# led-driver-v1.net
KiCad netlist of a schematic drawn in EAGLE
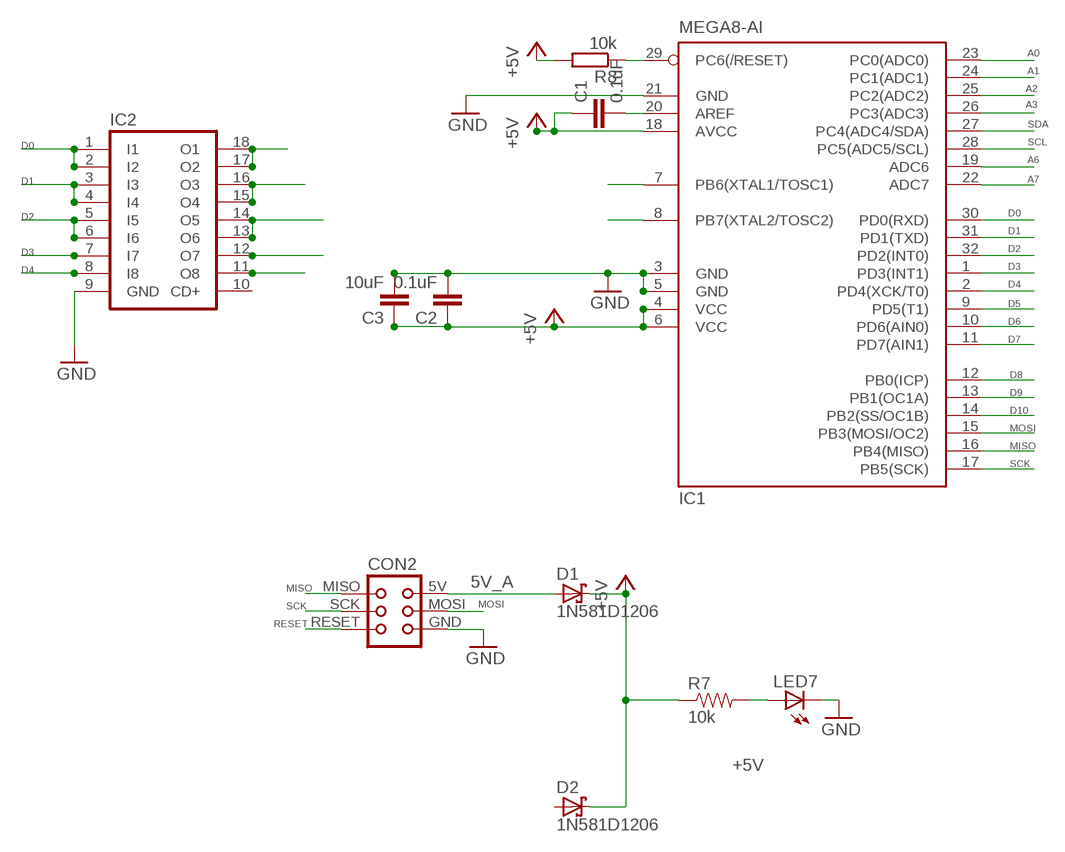
[diagram p0: schematic, sheet 1]

(export (version "E")
  (design (tool "Eeschema 10.0.6"))
  (components
    (comp (ref "C1")
      (value "0.1uF")
      (footprint "eagle-import:C1206")
      (libsource (lib "eagle-import") (part "C-EUC1206"))
    )
    (comp (ref "C2")
      (value "0.1uF")
      (footprint "eagle-import:C1206")
      (libsource (lib "eagle-import") (part "C-EUC1206"))
    )
    (comp (ref "C3")
      (value "10uF")
      (footprint "eagle-import:C1206")
      (libsource (lib "eagle-import") (part "C-EUC1206"))
    )
    (comp (ref "CON2")
      (value "TINYISPTAG")
      (footprint "eagle-import:TC2030-MCP")
      (libsource (lib "eagle-import") (part "TINYISPTAG"))
    )
    (comp (ref "D1")
      (value "1N581D1206")
      (footprint "eagle-import:LED-1206")
      (libsource (lib "eagle-import") (part "1N581D1206"))
    )
    (comp (ref "D2")
      (value "1N581D1206")
      (footprint "eagle-import:LED-1206")
      (libsource (lib "eagle-import") (part "1N581D1206"))
    )
    (comp (ref "IC1")
      (value "MEGA8-AI")
      (footprint "eagle-import:TQFP32-08")
      (fields (field (name "MPN") "ATMEGA8-16AU"))
      (libsource (lib "eagle-import") (part "MEGA8-AI"))
    )
    (comp (ref "IC2")
      (value "ULN2803A")
      (footprint "eagle-import:SO18W")
      (libsource (lib "eagle-import") (part "ULN2803A"))
    )
    (comp (ref "LED7")
      (value "LEDCHIP-LED0603")
      (footprint "eagle-import:CHIP-LED0603")
      (libsource (lib "eagle-import") (part "LEDCHIP-LED0603"))
    )
    (comp (ref "R7")
      (value "10k")
      (footprint "eagle-import:0603-RES")
      (libsource (lib "eagle-import") (part "RESISTOR0603-RES"))
    )
    (comp (ref "R8")
      (value "10k")
      (footprint "eagle-import:M1206")
      (libsource (lib "eagle-import") (part "R-EU_M1206"))
    )
  )
  (nets
    (net (code "1") (name "+5V") (class "Default")
      (node (ref "C1") (pin "1") (pinfunction "1_1") (pintype "passive"))
      (node (ref "C2") (pin "1") (pinfunction "1_1") (pintype "passive"))
      (node (ref "C3") (pin "1") (pinfunction "1_1") (pintype "passive"))
      (node (ref "D1") (pin "C") (pinfunction "C_C") (pintype "passive"))
      (node (ref "D2") (pin "C") (pinfunction "C_C") (pintype "passive"))
      (node (ref "IC1") (pin "18") (pinfunction "AVCC_18") (pintype "power_in"))
      (node (ref "IC1") (pin "4") (pinfunction "VCC_4") (pintype "power_in"))
      (node (ref "IC1") (pin "6") (pinfunction "VCC_6") (pintype "power_in"))
      (node (ref "R7") (pin "1") (pinfunction "1_1") (pintype "passive"))
      (node (ref "R8") (pin "2") (pinfunction "2_2") (pintype "passive"))
    )
    (net (code "2") (name "/5V_A") (class "Default")
      (node (ref "CON2") (pin "5V") (pinfunction "VCC_5V") (pintype "passive"))
      (node (ref "D1") (pin "A") (pinfunction "A_A") (pintype "passive"))
    )
    (net (code "3") (name "/A0") (class "Default")
      (node (ref "IC1") (pin "23") (pinfunction "PC0(ADC0)_23") (pintype "bidirectional"))
    )
    (net (code "4") (name "/A1") (class "Default")
      (node (ref "IC1") (pin "24") (pinfunction "PC1(ADC1)_24") (pintype "bidirectional"))
    )
    (net (code "5") (name "/A2") (class "Default")
      (node (ref "IC1") (pin "25") (pinfunction "PC2(ADC2)_25") (pintype "bidirectional"))
    )
    (net (code "6") (name "/A3") (class "Default")
      (node (ref "IC1") (pin "26") (pinfunction "PC3(ADC3)_26") (pintype "bidirectional"))
    )
    (net (code "7") (name "/A6") (class "Default")
      (node (ref "IC1") (pin "19") (pinfunction "ADC6_19") (pintype "bidirectional"))
    )
    (net (code "8") (name "/A7") (class "Default")
      (node (ref "IC1") (pin "22") (pinfunction "ADC7_22") (pintype "bidirectional"))
    )
    (net (code "9") (name "/D0") (class "Default")
      (node (ref "IC1") (pin "30") (pinfunction "PD0(RXD)_30") (pintype "bidirectional"))
      (node (ref "IC2") (pin "1") (pinfunction "I1_1") (pintype "input"))
      (node (ref "IC2") (pin "2") (pinfunction "I2_2") (pintype "input"))
    )
    (net (code "10") (name "/D1") (class "Default")
      (node (ref "IC1") (pin "31") (pinfunction "PD1(TXD)_31") (pintype "bidirectional"))
      (node (ref "IC2") (pin "3") (pinfunction "I3_3") (pintype "input"))
      (node (ref "IC2") (pin "4") (pinfunction "I4_4") (pintype "input"))
    )
    (net (code "11") (name "/D2") (class "Default")
      (node (ref "IC1") (pin "32") (pinfunction "PD2(INT0)_32") (pintype "bidirectional"))
      (node (ref "IC2") (pin "5") (pinfunction "I5_5") (pintype "input"))
      (node (ref "IC2") (pin "6") (pinfunction "I6_6") (pintype "input"))
    )
    (net (code "12") (name "/D3") (class "Default")
      (node (ref "IC1") (pin "1") (pinfunction "PD3(INT1)_1") (pintype "bidirectional"))
      (node (ref "IC2") (pin "7") (pinfunction "I7_7") (pintype "input"))
    )
    (net (code "13") (name "/D4") (class "Default")
      (node (ref "IC1") (pin "2") (pinfunction "PD4(XCK/T0)_2") (pintype "bidirectional"))
      (node (ref "IC2") (pin "8") (pinfunction "I8_8") (pintype "input"))
    )
    (net (code "14") (name "/D5") (class "Default")
      (node (ref "IC1") (pin "9") (pinfunction "PD5(T1)_9") (pintype "bidirectional"))
    )
    (net (code "15") (name "/D6") (class "Default")
      (node (ref "IC1") (pin "10") (pinfunction "PD6(AIN0)_10") (pintype "bidirectional"))
    )
    (net (code "16") (name "/D7") (class "Default")
      (node (ref "IC1") (pin "11") (pinfunction "PD7(AIN1)_11") (pintype "bidirectional"))
    )
    (net (code "17") (name "/D8") (class "Default")
      (node (ref "IC1") (pin "12") (pinfunction "PB0(ICP)_12") (pintype "bidirectional"))
    )
    (net (code "18") (name "/D9") (class "Default")
      (node (ref "IC1") (pin "13") (pinfunction "PB1(OC1A)_13") (pintype "bidirectional"))
    )
    (net (code "19") (name "/D10") (class "Default")
      (node (ref "IC1") (pin "14") (pinfunction "PB2(SS/OC1B)_14") (pintype "bidirectional"))
    )
    (net (code "20") (name "/MISO") (class "Default")
      (node (ref "CON2") (pin "MISO") (pinfunction "MISO_MISO") (pintype "passive"))
      (node (ref "IC1") (pin "16") (pinfunction "PB4(MISO)_16") (pintype "bidirectional"))
    )
    (net (code "21") (name "/MOSI") (class "Default")
      (node (ref "CON2") (pin "MOSI") (pinfunction "MOSI_MOSI") (pintype "passive"))
      (node (ref "IC1") (pin "15") (pinfunction "PB3(MOSI/OC2)_15") (pintype "bidirectional"))
    )
    (net (code "22") (name "/RESET") (class "Default")
      (node (ref "CON2") (pin "RESET") (pinfunction "RESET_RESET") (pintype "passive"))
      (node (ref "IC1") (pin "29") (pinfunction "PC6(/RESET)_29") (pintype "bidirectional"))
      (node (ref "R8") (pin "1") (pinfunction "1_1") (pintype "passive"))
    )
    (net (code "23") (name "/SCK") (class "Default")
      (node (ref "CON2") (pin "SCK") (pinfunction "SCK_SCK") (pintype "passive"))
      (node (ref "IC1") (pin "17") (pinfunction "PB5(SCK)_17") (pintype "bidirectional"))
    )
    (net (code "24") (name "/SCL") (class "Default")
      (node (ref "IC1") (pin "28") (pinfunction "PC5(ADC5/SCL)_28") (pintype "bidirectional"))
    )
    (net (code "25") (name "/SDA") (class "Default")
      (node (ref "IC1") (pin "27") (pinfunction "PC4(ADC4/SDA)_27") (pintype "bidirectional"))
    )
    (net (code "26") (name "GND") (class "Default")
      (node (ref "C2") (pin "2") (pinfunction "2_2") (pintype "passive"))
      (node (ref "C3") (pin "2") (pinfunction "2_2") (pintype "passive"))
      (node (ref "CON2") (pin "GND") (pinfunction "GND_GND") (pintype "passive"))
      (node (ref "IC1") (pin "21") (pinfunction "GND_21") (pintype "power_in"))
      (node (ref "IC1") (pin "3") (pinfunction "GND_3") (pintype "power_in"))
      (node (ref "IC1") (pin "5") (pinfunction "GND_5") (pintype "power_in"))
      (node (ref "IC2") (pin "9") (pinfunction "GND_9") (pintype "power_in"))
      (node (ref "LED7") (pin "C") (pinfunction "C_C") (pintype "passive"))
    )
    (net (code "27") (name "Net-(IC1-AREF)") (class "Default")
      (node (ref "C1") (pin "2") (pinfunction "2_2") (pintype "passive"))
      (node (ref "IC1") (pin "20") (pinfunction "AREF_20") (pintype "passive"))
    )
    (net (code "28") (name "Net-(IC2-O1)") (class "Default")
      (node (ref "IC2") (pin "17") (pinfunction "O2_17") (pintype "open_collector"))
      (node (ref "IC2") (pin "18") (pinfunction "O1_18") (pintype "open_collector"))
    )
    (net (code "29") (name "Net-(IC2-O3)") (class "Default")
      (node (ref "IC2") (pin "15") (pinfunction "O4_15") (pintype "open_collector"))
      (node (ref "IC2") (pin "16") (pinfunction "O3_16") (pintype "open_collector"))
    )
    (net (code "30") (name "Net-(IC2-O5)") (class "Default")
      (node (ref "IC2") (pin "13") (pinfunction "O6_13") (pintype "open_collector"))
      (node (ref "IC2") (pin "14") (pinfunction "O5_14") (pintype "open_collector"))
    )
    (net (code "31") (name "Net-(LED7-PadA)") (class "Default")
      (node (ref "LED7") (pin "A") (pinfunction "A_A") (pintype "passive"))
      (node (ref "R7") (pin "2") (pinfunction "2_2") (pintype "passive"))
    )
    (net (code "32") (name "unconnected-(D2-PadA)") (class "Default")
      (node (ref "D2") (pin "A") (pinfunction "A_A") (pintype "passive"))
    )
    (net (code "33") (name "unconnected-(IC1-PB6(XTAL1{slash}TOSC1)-Pad7)") (class "Default")
      (node (ref "IC1") (pin "7") (pinfunction "PB6(XTAL1/TOSC1)_7") (pintype "bidirectional"))
    )
    (net (code "34") (name "unconnected-(IC1-PB7(XTAL2{slash}TOSC2)-Pad8)") (class "Default")
      (node (ref "IC1") (pin "8") (pinfunction "PB7(XTAL2/TOSC2)_8") (pintype "bidirectional"))
    )
    (net (code "35") (name "unconnected-(IC2-CD+-Pad10)") (class "Default")
      (node (ref "IC2") (pin "10") (pinfunction "CD+_10") (pintype "passive"))
    )
    (net (code "36") (name "unconnected-(IC2-O7-Pad12)") (class "Default")
      (node (ref "IC2") (pin "12") (pinfunction "O7_12") (pintype "open_collector"))
    )
    (net (code "37") (name "unconnected-(IC2-O8-Pad11)") (class "Default")
      (node (ref "IC2") (pin "11") (pinfunction "O8_11") (pintype "open_collector"))
    )
  )
)
